# HF_AMP.net
KiCad netlist of a schematic drawn in Altium Designer
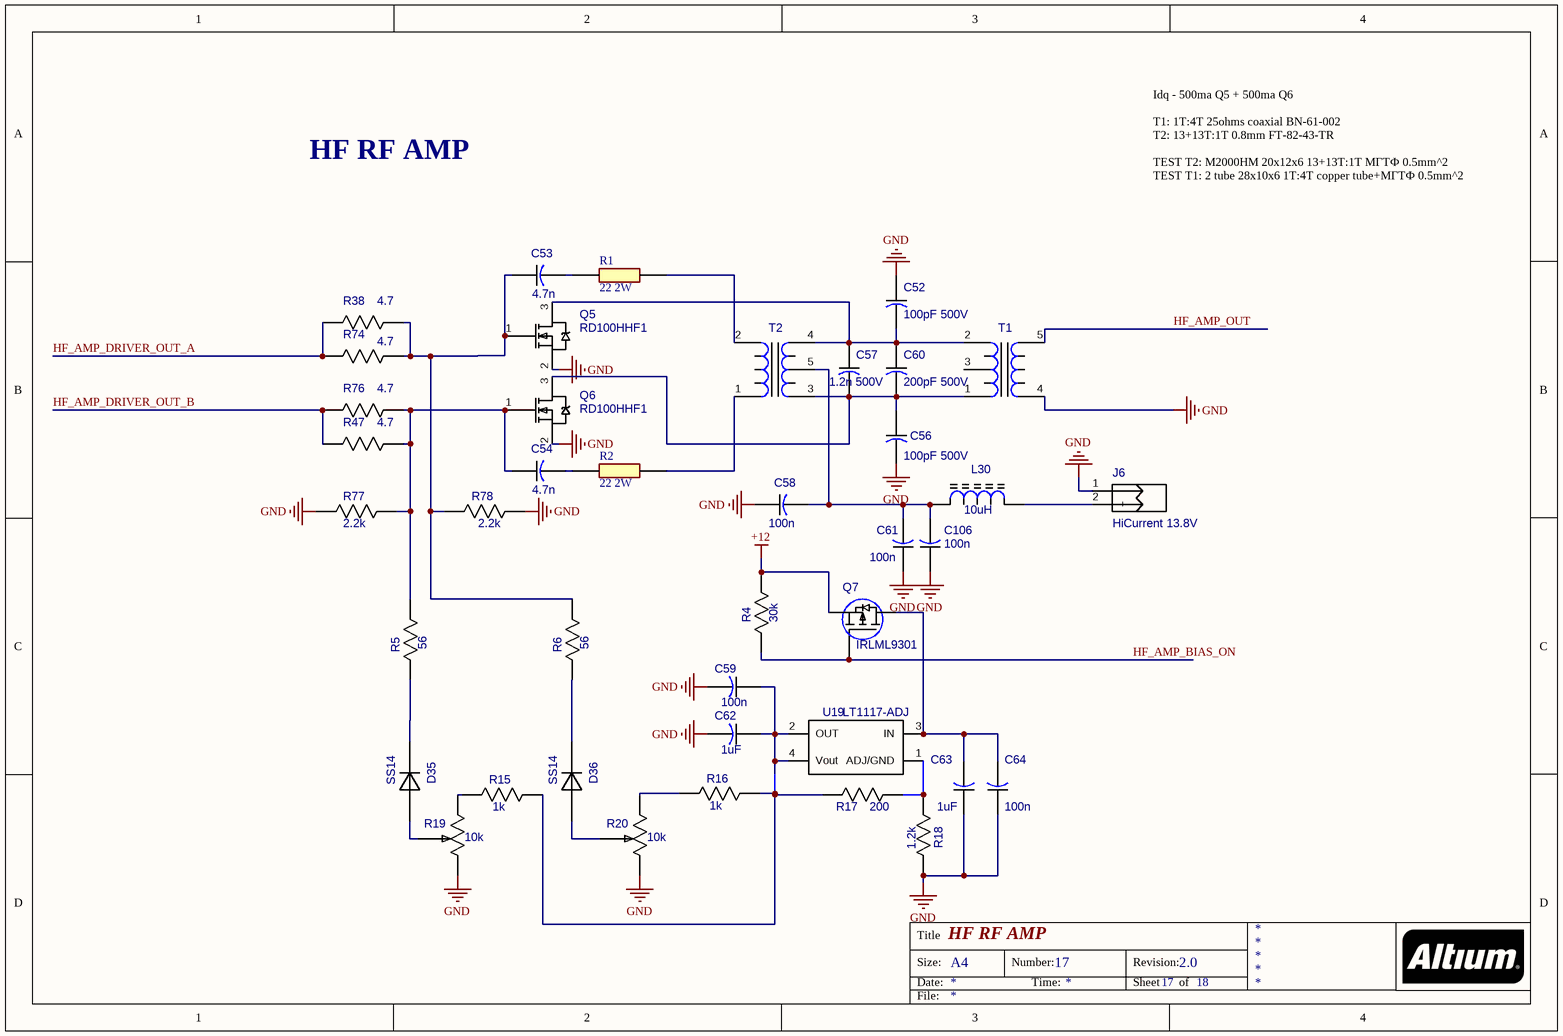
[diagram p0: HF_AMP.SchDoc]

(export (version "E")
  (design (tool "Eeschema 10.0.6"))
  (components
    (comp (ref "C52")
      (value "100pF 500V")
      (footprint "CAP_1206")
      (description "CAP_1206")
      (libsource (lib "*") (part "CAP_1206"))
    )
    (comp (ref "C53")
      (value "4.7n")
      (footprint "CAP_1206")
      (description "CAP_1206")
      (libsource (lib "*") (part "CAP_1206"))
    )
    (comp (ref "C54")
      (value "4.7n")
      (footprint "CAP_1206")
      (description "CAP_1206")
      (libsource (lib "*") (part "CAP_1206"))
    )
    (comp (ref "C56")
      (value "100pF 500V")
      (footprint "CAP_1206")
      (description "CAP_1206")
      (libsource (lib "*") (part "CAP_1206"))
    )
    (comp (ref "C57")
      (value "1.2n 500V")
      (footprint "CAP_1206")
      (description "CAP_1206")
      (libsource (lib "*") (part "CAP_1206"))
    )
    (comp (ref "C58")
      (value "100n")
      (footprint "CAP_1206")
      (description "CAP_1206")
      (libsource (lib "*") (part "CAP_1206"))
    )
    (comp (ref "C59")
      (value "100n")
      (footprint "CAP_0805")
      (description "CAP_0805")
      (libsource (lib "*") (part "CAP_0805"))
    )
    (comp (ref "C60")
      (value "200pF 500V")
      (footprint "CAP_1206")
      (description "CAP_1206")
      (libsource (lib "*") (part "CAP_1206"))
    )
    (comp (ref "C61")
      (value "100n")
      (footprint "CAP_1206")
      (description "CAP_1206")
      (libsource (lib "*") (part "CAP_1206"))
    )
    (comp (ref "C62")
      (value "1uF")
      (footprint "CAP_0805")
      (description "CAP_0805")
      (libsource (lib "*") (part "CAP_0805"))
    )
    (comp (ref "C63")
      (value "1uF")
      (footprint "CAP_0805")
      (description "CAP_0805")
      (libsource (lib "*") (part "CAP_0805"))
    )
    (comp (ref "C64")
      (value "100n")
      (footprint "CAP_0805")
      (description "CAP_0805")
      (libsource (lib "*") (part "CAP_0805"))
    )
    (comp (ref "C106")
      (value "100n")
      (footprint "CAP_1206")
      (description "CAP_1206")
      (libsource (lib "*") (part "CAP_1206"))
    )
    (comp (ref "D35") (value "SS14") (footprint "SS14") (libsource (lib "*") (part "SS14")))
    (comp (ref "D36") (value "SS14") (footprint "SS14") (libsource (lib "*") (part "SS14")))
    (comp (ref "J6")
      (value "HiCurrent 13.8V")
      (footprint "1986717-2")
      (description "JX2")
      (libsource (lib "*") (part "1986717-2"))
    )
    (comp (ref "L30")
      (value "10uH")
      (footprint "IND_FERRITE_CORE")
      (description "Inductor")
      (libsource (lib "*") (part "IND_FERRITE_CORE"))
    )
    (comp (ref "Q5")
      (value "RD100HHF1")
      (footprint "RD100_V2")
      (libsource (lib "RF-UNIT-BIG") (part "RD100HHF1"))
    )
    (comp (ref "Q6")
      (value "RD100HHF1")
      (footprint "RD100_V2")
      (libsource (lib "RF-UNIT-BIG") (part "RD100HHF1"))
    )
    (comp (ref "Q7")
      (value "IRLML9301")
      (footprint "SOT23")
      (description "MOSFET")
      (libsource (lib "*") (part "MOSFET_ENH_PD"))
    )
    (comp (ref "R1")
      (value "22 2W")
      (footprint "RES-2W")
      (description "CFR200J100R")
      (fields (field (name "MOUSER PART NUMBER") "279-CFR200J100R"))
      (libsource (lib "RF-UNIT-BIG") (part "CFR200J100R"))
    )
    (comp (ref "R2")
      (value "22 2W")
      (footprint "RES-2W")
      (description "CFR200J100R")
      (fields (field (name "MOUSER PART NUMBER") "279-CFR200J100R"))
      (libsource (lib "RF-UNIT-BIG") (part "CFR200J100R"))
    )
    (comp (ref "R4")
      (value "30k")
      (footprint "RES_0805")
      (description "RES_0805")
      (libsource (lib "*") (part "RES_0805"))
    )
    (comp (ref "R5")
      (value "56")
      (footprint "RES_0805")
      (description "RES_0805")
      (libsource (lib "*") (part "RES_0805"))
    )
    (comp (ref "R6")
      (value "56")
      (footprint "RES_0805")
      (description "RES_0805")
      (libsource (lib "*") (part "RES_0805"))
    )
    (comp (ref "R15")
      (value "1k")
      (footprint "RES_0805")
      (description "RES_0805")
      (libsource (lib "*") (part "RES_0805"))
    )
    (comp (ref "R16")
      (value "1k")
      (footprint "RES_0805")
      (description "RES_0805")
      (libsource (lib "*") (part "RES_0805"))
    )
    (comp (ref "R17")
      (value "200")
      (footprint "RES_0805")
      (description "RES_0805")
      (libsource (lib "*") (part "RES_0805"))
    )
    (comp (ref "R18")
      (value "1.2k")
      (footprint "RES_0805")
      (description "RES_0805")
      (libsource (lib "*") (part "RES_0805"))
    )
    (comp (ref "R19")
      (value "10k")
      (footprint "306J")
      (description "306J")
      (fields (field (name "Comment") "ADJ-10k"))
      (libsource (lib "*") (part "306J"))
    )
    (comp (ref "R20")
      (value "10k")
      (footprint "306J")
      (description "306J")
      (fields (field (name "Comment") "ADJ-10k"))
      (libsource (lib "*") (part "306J"))
    )
    (comp (ref "R38")
      (value "4.7")
      (footprint "RES_1206")
      (description "RES_1206")
      (libsource (lib "*") (part "RES_1206"))
    )
    (comp (ref "R47")
      (value "4.7")
      (footprint "RES_1206")
      (description "RES_1206")
      (libsource (lib "*") (part "RES_1206"))
    )
    (comp (ref "R74")
      (value "4.7")
      (footprint "RES_1206")
      (description "RES_1206")
      (libsource (lib "*") (part "RES_1206"))
    )
    (comp (ref "R76")
      (value "4.7")
      (footprint "RES_1206")
      (description "RES_1206")
      (libsource (lib "*") (part "RES_1206"))
    )
    (comp (ref "R77")
      (value "2.2k")
      (footprint "RES_0805")
      (description "RES_0805")
      (libsource (lib "*") (part "RES_0805"))
    )
    (comp (ref "R78")
      (value "2.2k")
      (footprint "RES_0805")
      (description "RES_0805")
      (libsource (lib "*") (part "RES_0805"))
    )
    (comp (ref "T1")
      (value "TRANSF_HF2")
      (footprint "TRANSF_HF2-3")
      (libsource (lib "RF-UNIT-BIG") (part "TRANSF_RF2"))
    )
    (comp (ref "T2")
      (value "TRANSF_HF1")
      (footprint "TRANSF_HF1")
      (libsource (lib "RF-UNIT-BIG") (part "TRANSF_RF1"))
    )
    (comp (ref "U19")
      (value "LT1117-ADJ")
      (footprint "LT1117IST-ADJ")
      (description "LT1117IST-ADJ")
      (libsource (lib "*") (part "LT1117IST-ADJ"))
    )
  )
  (nets
    (net (code "1") (name "+12") (class "Default")
      (node (ref "Q7") (pin "2") (pinfunction "S_2") (pintype "passive"))
      (node (ref "R4") (pin "2") (pinfunction "2_2") (pintype "passive"))
    )
    (net (code "2") (name "/HF_AMP_BIAS_ON") (class "Default")
      (node (ref "Q7") (pin "1") (pinfunction "G_1") (pintype "passive"))
      (node (ref "R4") (pin "1") (pinfunction "1_1") (pintype "passive"))
    )
    (net (code "3") (name "/HF_AMP_DRIVER_OUT_A") (class "Default")
      (node (ref "R38") (pin "1") (pinfunction "1_1") (pintype "passive"))
      (node (ref "R74") (pin "1") (pinfunction "1_1") (pintype "passive"))
    )
    (net (code "4") (name "/HF_AMP_DRIVER_OUT_B") (class "Default")
      (node (ref "R47") (pin "1") (pinfunction "1_1") (pintype "passive"))
      (node (ref "R76") (pin "1") (pinfunction "1_1") (pintype "passive"))
    )
    (net (code "5") (name "/HF_AMP_OUT") (class "Default")
      (node (ref "T1") (pin "5") (pinfunction "S2_5") (pintype "passive"))
    )
    (net (code "6") (name "GND") (class "Default")
      (node (ref "C106") (pin "1") (pinfunction "1_1") (pintype "passive"))
      (node (ref "C52") (pin "1") (pinfunction "1_1") (pintype "passive"))
      (node (ref "C56") (pin "2") (pinfunction "2_2") (pintype "passive"))
      (node (ref "C58") (pin "1") (pinfunction "1_1") (pintype "passive"))
      (node (ref "C59") (pin "2") (pinfunction "2_2") (pintype "passive"))
      (node (ref "C61") (pin "1") (pinfunction "1_1") (pintype "passive"))
      (node (ref "C62") (pin "2") (pinfunction "2_2") (pintype "passive"))
      (node (ref "C63") (pin "1") (pinfunction "1_1") (pintype "passive"))
      (node (ref "C64") (pin "1") (pinfunction "1_1") (pintype "passive"))
      (node (ref "J6") (pin "1") (pinfunction "-_1") (pintype "passive"))
      (node (ref "Q5") (pin "2") (pinfunction "S_2") (pintype "passive"))
      (node (ref "Q6") (pin "2") (pinfunction "S_2") (pintype "passive"))
      (node (ref "R18") (pin "2") (pinfunction "2_2") (pintype "passive"))
      (node (ref "R19") (pin "1") (pinfunction "CCW_1") (pintype "passive"))
      (node (ref "R20") (pin "1") (pinfunction "CCW_1") (pintype "passive"))
      (node (ref "R77") (pin "1") (pinfunction "1_1") (pintype "passive"))
      (node (ref "R78") (pin "2") (pinfunction "2_2") (pintype "passive"))
      (node (ref "T1") (pin "4") (pinfunction "S1_4") (pintype "passive"))
    )
    (net (code "7") (name "Net-(C53-Pad2)") (class "Default")
      (node (ref "C53") (pin "2") (pinfunction "2_2") (pintype "passive"))
      (node (ref "R1") (pin "1") (pinfunction "1_1") (pintype "passive"))
    )
    (net (code "8") (name "Net-(C54-Pad2)") (class "Default")
      (node (ref "C54") (pin "2") (pinfunction "2_2") (pintype "passive"))
      (node (ref "R2") (pin "1") (pinfunction "1_1") (pintype "passive"))
    )
    (net (code "9") (name "Net-(D35-A)") (class "Default")
      (node (ref "D35") (pin "2") (pinfunction "A_2") (pintype "passive"))
      (node (ref "R19") (pin "2") (pinfunction "W_2") (pintype "passive"))
    )
    (net (code "10") (name "Net-(D35-K)") (class "Default")
      (node (ref "D35") (pin "1") (pinfunction "K_1") (pintype "passive"))
      (node (ref "R5") (pin "1") (pinfunction "1_1") (pintype "passive"))
    )
    (net (code "11") (name "Net-(D36-A)") (class "Default")
      (node (ref "D36") (pin "2") (pinfunction "A_2") (pintype "passive"))
      (node (ref "R20") (pin "2") (pinfunction "W_2") (pintype "passive"))
    )
    (net (code "12") (name "Net-(D36-K)") (class "Default")
      (node (ref "D36") (pin "1") (pinfunction "K_1") (pintype "passive"))
      (node (ref "R6") (pin "1") (pinfunction "1_1") (pintype "passive"))
    )
    (net (code "13") (name "Net-(J6-+)") (class "Default")
      (node (ref "J6") (pin "2") (pinfunction "+_2") (pintype "passive"))
      (node (ref "L30") (pin "2") (pinfunction "B_2") (pintype "passive"))
    )
    (net (code "14") (name "Net-(L30-A)") (class "Default")
      (node (ref "C106") (pin "2") (pinfunction "2_2") (pintype "passive"))
      (node (ref "C58") (pin "2") (pinfunction "2_2") (pintype "passive"))
      (node (ref "C61") (pin "2") (pinfunction "2_2") (pintype "passive"))
      (node (ref "L30") (pin "1") (pinfunction "A_1") (pintype "passive"))
      (node (ref "T2") (pin "5") (pinfunction "S3_5") (pintype "passive"))
    )
    (net (code "15") (name "Net-(Q5-D)") (class "Default")
      (node (ref "C52") (pin "2") (pinfunction "2_2") (pintype "passive"))
      (node (ref "C57") (pin "1") (pinfunction "1_1") (pintype "passive"))
      (node (ref "C60") (pin "1") (pinfunction "1_1") (pintype "passive"))
      (node (ref "Q5") (pin "3") (pinfunction "D_3") (pintype "passive"))
      (node (ref "T1") (pin "2") (pinfunction "P2_2") (pintype "passive"))
      (node (ref "T2") (pin "4") (pinfunction "S2_4") (pintype "passive"))
    )
    (net (code "16") (name "Net-(Q5-G)") (class "Default")
      (node (ref "C53") (pin "1") (pinfunction "1_1") (pintype "passive"))
      (node (ref "Q5") (pin "1") (pinfunction "G_1") (pintype "passive"))
      (node (ref "R38") (pin "2") (pinfunction "2_2") (pintype "passive"))
      (node (ref "R6") (pin "2") (pinfunction "2_2") (pintype "passive"))
      (node (ref "R74") (pin "2") (pinfunction "2_2") (pintype "passive"))
      (node (ref "R78") (pin "1") (pinfunction "1_1") (pintype "passive"))
    )
    (net (code "17") (name "Net-(Q6-D)") (class "Default")
      (node (ref "C56") (pin "1") (pinfunction "1_1") (pintype "passive"))
      (node (ref "C57") (pin "2") (pinfunction "2_2") (pintype "passive"))
      (node (ref "C60") (pin "2") (pinfunction "2_2") (pintype "passive"))
      (node (ref "Q6") (pin "3") (pinfunction "D_3") (pintype "passive"))
      (node (ref "T1") (pin "1") (pinfunction "P1_1") (pintype "passive"))
      (node (ref "T2") (pin "3") (pinfunction "S1_3") (pintype "passive"))
    )
    (net (code "18") (name "Net-(Q6-G)") (class "Default")
      (node (ref "C54") (pin "1") (pinfunction "1_1") (pintype "passive"))
      (node (ref "Q6") (pin "1") (pinfunction "G_1") (pintype "passive"))
      (node (ref "R47") (pin "2") (pinfunction "2_2") (pintype "passive"))
      (node (ref "R5") (pin "2") (pinfunction "2_2") (pintype "passive"))
      (node (ref "R76") (pin "2") (pinfunction "2_2") (pintype "passive"))
      (node (ref "R77") (pin "2") (pinfunction "2_2") (pintype "passive"))
    )
    (net (code "19") (name "Net-(Q7-D)") (class "Default")
      (node (ref "C63") (pin "2") (pinfunction "2_2") (pintype "passive"))
      (node (ref "C64") (pin "2") (pinfunction "2_2") (pintype "passive"))
      (node (ref "Q7") (pin "3") (pinfunction "D_3") (pintype "passive"))
      (node (ref "U19") (pin "3") (pinfunction "IN_3") (pintype "passive"))
    )
    (net (code "20") (name "Net-(R19-CW)") (class "Default")
      (node (ref "R15") (pin "1") (pinfunction "1_1") (pintype "passive"))
      (node (ref "R19") (pin "3") (pinfunction "CW_3") (pintype "passive"))
    )
    (net (code "21") (name "Net-(R20-CW)") (class "Default")
      (node (ref "R16") (pin "1") (pinfunction "1_1") (pintype "passive"))
      (node (ref "R20") (pin "3") (pinfunction "CW_3") (pintype "passive"))
    )
    (net (code "22") (name "Net-(T2-P1)") (class "Default")
      (node (ref "R2") (pin "2") (pinfunction "2_2") (pintype "passive"))
      (node (ref "T2") (pin "1") (pinfunction "P1_1") (pintype "passive"))
    )
    (net (code "23") (name "Net-(T2-P2)") (class "Default")
      (node (ref "R1") (pin "2") (pinfunction "2_2") (pintype "passive"))
      (node (ref "T2") (pin "2") (pinfunction "P2_2") (pintype "passive"))
    )
    (net (code "24") (name "Net-(U19-ADJ{slash}GND)") (class "Default")
      (node (ref "R17") (pin "2") (pinfunction "2_2") (pintype "passive"))
      (node (ref "R18") (pin "1") (pinfunction "1_1") (pintype "passive"))
      (node (ref "U19") (pin "1") (pinfunction "ADJ/GND_1") (pintype "passive"))
    )
    (net (code "25") (name "Net-(U19-OUT)") (class "Default")
      (node (ref "C59") (pin "1") (pinfunction "1_1") (pintype "passive"))
      (node (ref "C62") (pin "1") (pinfunction "1_1") (pintype "passive"))
      (node (ref "R15") (pin "2") (pinfunction "2_2") (pintype "passive"))
      (node (ref "R16") (pin "2") (pinfunction "2_2") (pintype "passive"))
      (node (ref "R17") (pin "1") (pinfunction "1_1") (pintype "passive"))
      (node (ref "U19") (pin "2") (pinfunction "OUT_2") (pintype "passive"))
      (node (ref "U19") (pin "4") (pinfunction "Vout_4") (pintype "passive"))
    )
    (net (code "26") (name "unconnected-(T1-P3-Pad3)") (class "Default")
      (node (ref "T1") (pin "3") (pinfunction "P3_3") (pintype "passive"))
    )
  )
)
